# Evap-Lite_V2_1.net
KiCad netlist of a schematic drawn in EAGLE
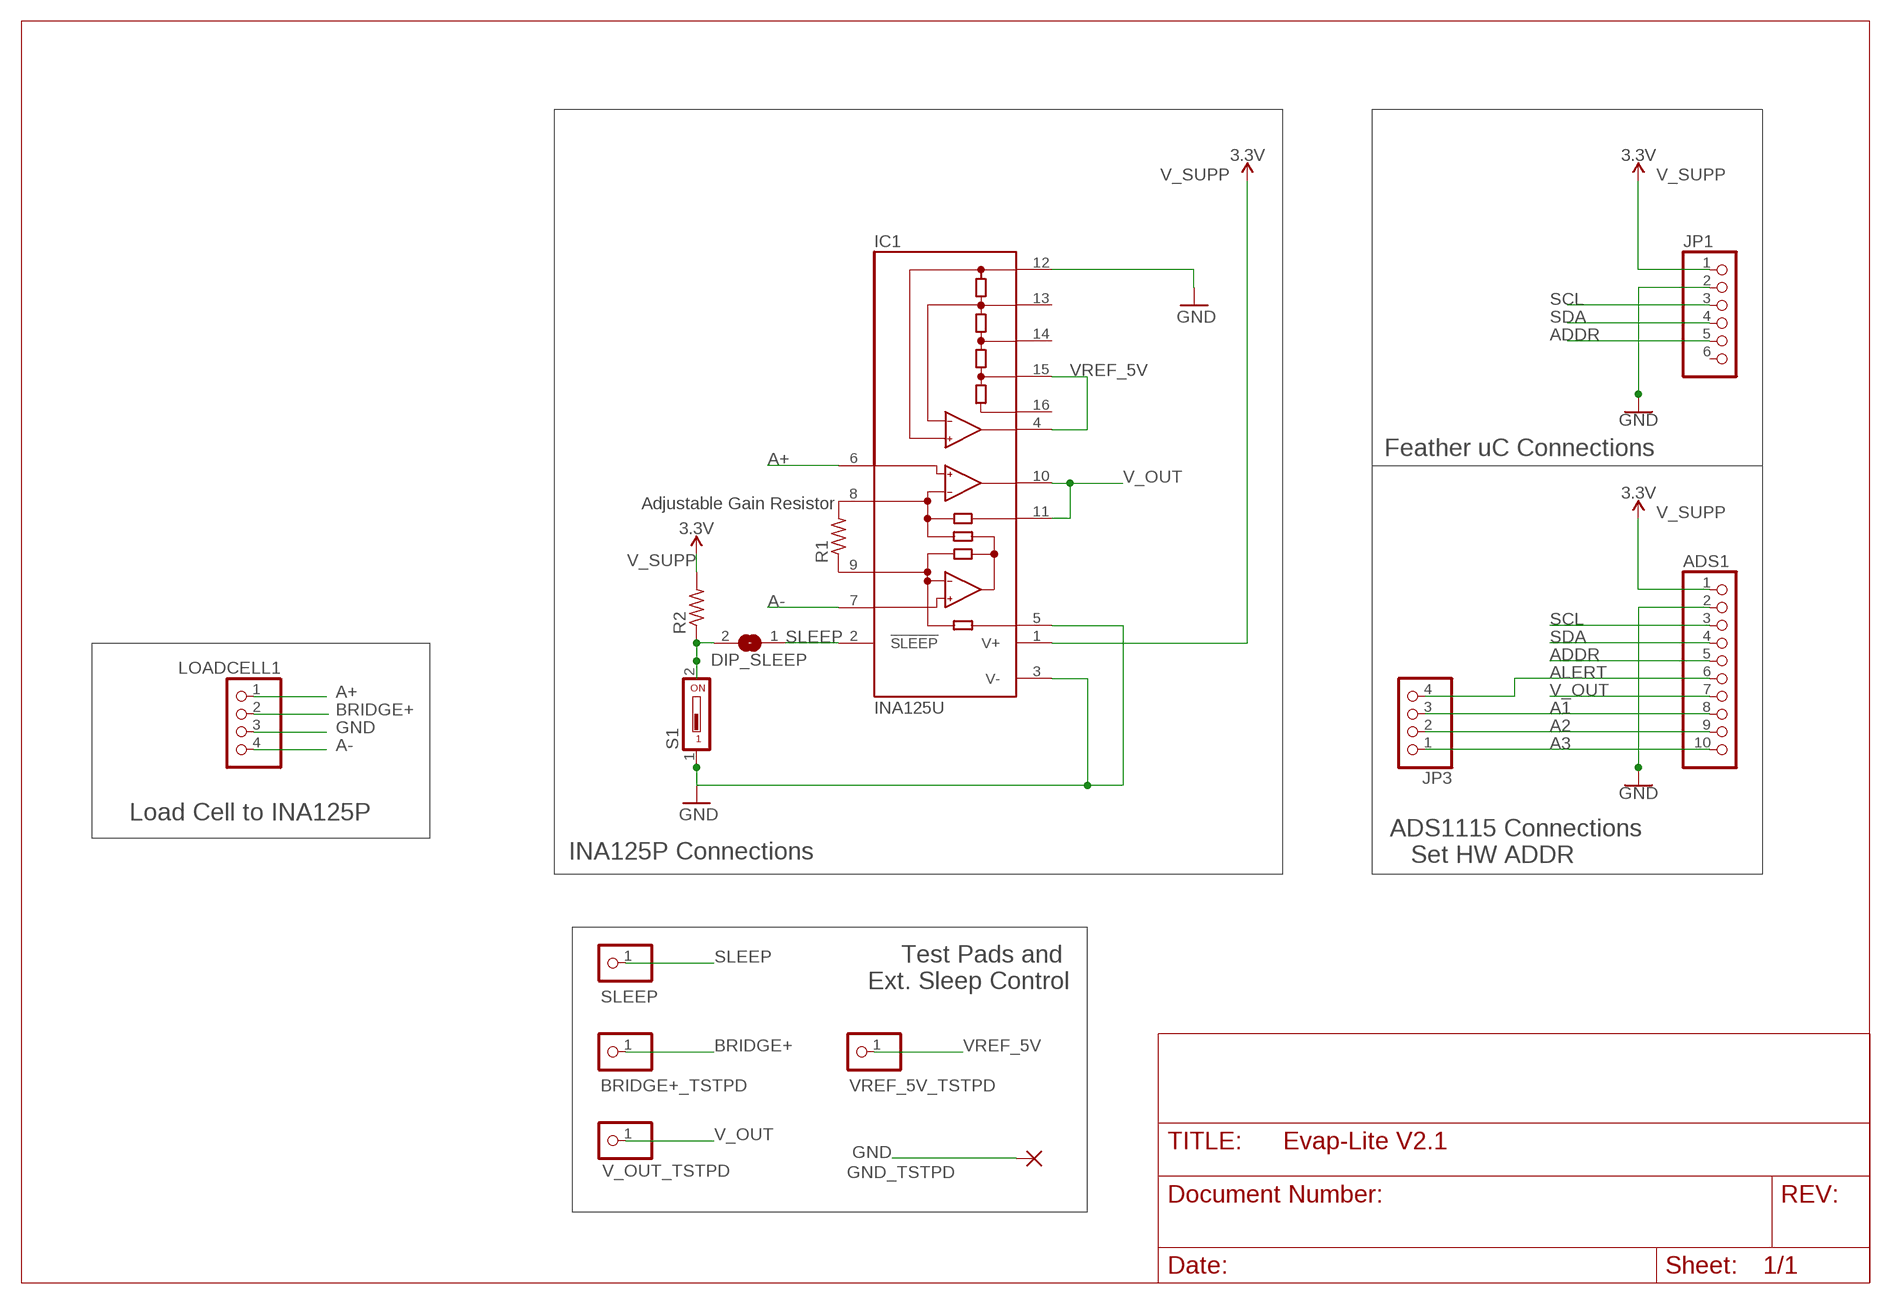
[diagram p0: schematic, sheet 1]

(export (version "E")
  (design (tool "Eeschema 10.0.6"))
  (components
    (comp (ref "ADS1")
      (value "PINHD-1X10")
      (footprint "eagle-import:1X10")
      (libsource (lib "eagle-import") (part "PINHD-1X10"))
    )
    (comp (ref "BRIDGE+_TSTPD")
      (value "PINHD-1X1")
      (footprint "eagle-import:1X01")
      (libsource (lib "eagle-import") (part "PINHD-1X1"))
    )
    (comp (ref "DIP_SLEEP")
      (value "SJ")
      (footprint "eagle-import:SJ")
      (libsource (lib "eagle-import") (part "SJ"))
    )
    (comp (ref "GND_TSTPD")
      (value "WIREPADSMD2,54-5,08")
      (footprint "eagle-import:SMD2,54-5,08")
      (libsource (lib "eagle-import") (part "WIREPADSMD2,54-5,08"))
    )
    (comp (ref "IC1")
      (value "INA125U")
      (footprint "eagle-import:SO16-1")
      (fields (field (name "MF") "TEXAS INSTRUMENT CONNECTORS"))
      (libsource (lib "eagle-import") (part "INA125U"))
    )
    (comp (ref "JP1")
      (value "PINHD-1X6")
      (footprint "eagle-import:1X06")
      (libsource (lib "eagle-import") (part "PINHD-1X6"))
    )
    (comp (ref "JP3")
      (value "PINHD-1X4")
      (footprint "eagle-import:1X04")
      (libsource (lib "eagle-import") (part "PINHD-1X4"))
    )
    (comp (ref "LOADCELL1")
      (value "PINHD-1X4")
      (footprint "eagle-import:1X04")
      (libsource (lib "eagle-import") (part "PINHD-1X4"))
    )
    (comp (ref "R1")
      (value "R-US_R0603")
      (footprint "eagle-import:R0603")
      (libsource (lib "eagle-import") (part "R-US_R0603"))
    )
    (comp (ref "R2")
      (value "R-US_R1206")
      (footprint "eagle-import:R1206")
      (libsource (lib "eagle-import") (part "R-US_R1206"))
    )
    (comp (ref "S1")
      (value "DS01")
      (footprint "eagle-import:DS-01")
      (libsource (lib "eagle-import") (part "DS01"))
    )
    (comp (ref "SLEEP")
      (value "PINHD-1X1")
      (footprint "eagle-import:1X01")
      (libsource (lib "eagle-import") (part "PINHD-1X1"))
    )
    (comp (ref "VREF_5V_TSTPD")
      (value "PINHD-1X1")
      (footprint "eagle-import:1X01")
      (libsource (lib "eagle-import") (part "PINHD-1X1"))
    )
    (comp (ref "V_OUT_TSTPD")
      (value "PINHD-1X1")
      (footprint "eagle-import:1X01")
      (libsource (lib "eagle-import") (part "PINHD-1X1"))
    )
  )
  (nets
    (net (code "1") (name "/A+") (class "Default")
      (node (ref "IC1") (pin "6") (pinfunction "+IN_6") (pintype "input"))
      (node (ref "LOADCELL1") (pin "1") (pinfunction "1_1") (pintype "passive"))
    )
    (net (code "2") (name "/A-") (class "Default")
      (node (ref "IC1") (pin "7") (pinfunction "-IN_7") (pintype "input"))
      (node (ref "LOADCELL1") (pin "4") (pinfunction "4_4") (pintype "passive"))
    )
    (net (code "3") (name "/A1") (class "Default")
      (node (ref "ADS1") (pin "8") (pinfunction "8_8") (pintype "passive"))
      (node (ref "JP3") (pin "3") (pinfunction "3_3") (pintype "passive"))
    )
    (net (code "4") (name "/A2") (class "Default")
      (node (ref "ADS1") (pin "9") (pinfunction "9_9") (pintype "passive"))
      (node (ref "JP3") (pin "2") (pinfunction "2_2") (pintype "passive"))
    )
    (net (code "5") (name "/A3") (class "Default")
      (node (ref "ADS1") (pin "10") (pinfunction "10_10") (pintype "passive"))
      (node (ref "JP3") (pin "1") (pinfunction "1_1") (pintype "passive"))
    )
    (net (code "6") (name "/ADDR") (class "Default")
      (node (ref "ADS1") (pin "5") (pinfunction "5_5") (pintype "passive"))
      (node (ref "JP1") (pin "5") (pinfunction "5_5") (pintype "passive"))
    )
    (net (code "7") (name "/ALERT") (class "Default")
      (node (ref "ADS1") (pin "6") (pinfunction "6_6") (pintype "passive"))
      (node (ref "JP3") (pin "4") (pinfunction "4_4") (pintype "passive"))
    )
    (net (code "8") (name "/BRIDGE+") (class "Default")
      (node (ref "BRIDGE+_TSTPD") (pin "1") (pinfunction "1_1") (pintype "passive"))
      (node (ref "LOADCELL1") (pin "2") (pinfunction "2_2") (pintype "passive"))
    )
    (net (code "9") (name "/SCL") (class "Default")
      (node (ref "ADS1") (pin "3") (pinfunction "3_3") (pintype "passive"))
      (node (ref "JP1") (pin "3") (pinfunction "3_3") (pintype "passive"))
    )
    (net (code "10") (name "/SDA") (class "Default")
      (node (ref "ADS1") (pin "4") (pinfunction "4_4") (pintype "passive"))
      (node (ref "JP1") (pin "4") (pinfunction "4_4") (pintype "passive"))
    )
    (net (code "11") (name "/SLEEP") (class "Default")
      (node (ref "DIP_SLEEP") (pin "1") (pinfunction "1_1") (pintype "passive"))
      (node (ref "IC1") (pin "2") (pinfunction "~{SLEEP}_2") (pintype "input"))
      (node (ref "SLEEP") (pin "1") (pinfunction "1_1") (pintype "passive"))
    )
    (net (code "12") (name "/VREF_5V") (class "Default")
      (node (ref "IC1") (pin "15") (pinfunction "REF5_15") (pintype "output"))
      (node (ref "IC1") (pin "4") (pinfunction "REFOUT_4") (pintype "output"))
      (node (ref "VREF_5V_TSTPD") (pin "1") (pinfunction "1_1") (pintype "passive"))
    )
    (net (code "13") (name "/V_OUT") (class "Default")
      (node (ref "ADS1") (pin "7") (pinfunction "7_7") (pintype "passive"))
      (node (ref "IC1") (pin "10") (pinfunction "OUT_10") (pintype "output"))
      (node (ref "IC1") (pin "11") (pinfunction "SENSE_11") (pintype "passive"))
      (node (ref "V_OUT_TSTPD") (pin "1") (pinfunction "1_1") (pintype "passive"))
    )
    (net (code "14") (name "3.3V") (class "Default")
      (node (ref "ADS1") (pin "1") (pinfunction "1_1") (pintype "passive"))
      (node (ref "IC1") (pin "1") (pinfunction "V+_1") (pintype "power_in"))
      (node (ref "JP1") (pin "1") (pinfunction "1_1") (pintype "passive"))
      (node (ref "R2") (pin "2") (pinfunction "2_2") (pintype "passive"))
    )
    (net (code "15") (name "GND") (class "Default")
      (node (ref "ADS1") (pin "2") (pinfunction "2_2") (pintype "passive"))
      (node (ref "GND_TSTPD") (pin "1") (pinfunction "P_1") (pintype "passive"))
      (node (ref "IC1") (pin "12") (pinfunction "REFCOM_12") (pintype "passive"))
      (node (ref "IC1") (pin "3") (pinfunction "V-_3") (pintype "power_in"))
      (node (ref "IC1") (pin "5") (pinfunction "REF_5") (pintype "passive"))
      (node (ref "JP1") (pin "2") (pinfunction "2_2") (pintype "passive"))
      (node (ref "LOADCELL1") (pin "3") (pinfunction "3_3") (pintype "passive"))
      (node (ref "S1") (pin "1") (pinfunction "1_1") (pintype "passive"))
    )
    (net (code "16") (name "Net-(DIP_SLEEP-Pad2)") (class "Default")
      (node (ref "DIP_SLEEP") (pin "2") (pinfunction "2_2") (pintype "passive"))
      (node (ref "R2") (pin "1") (pinfunction "1_1") (pintype "passive"))
      (node (ref "S1") (pin "2") (pinfunction "2_2") (pintype "passive"))
    )
    (net (code "17") (name "Net-(IC1-RG-Pad8)") (class "Default")
      (node (ref "IC1") (pin "8") (pinfunction "RG_8") (pintype "passive"))
      (node (ref "R1") (pin "2") (pinfunction "2_2") (pintype "passive"))
    )
    (net (code "18") (name "Net-(IC1-RG-Pad9)") (class "Default")
      (node (ref "IC1") (pin "9") (pinfunction "RG_9") (pintype "passive"))
      (node (ref "R1") (pin "1") (pinfunction "1_1") (pintype "passive"))
    )
    (net (code "19") (name "unconnected-(IC1-REF2.5-Pad14)") (class "Default")
      (node (ref "IC1") (pin "14") (pinfunction "REF2.5_14") (pintype "output"))
    )
    (net (code "20") (name "unconnected-(IC1-REF10-Pad16)") (class "Default")
      (node (ref "IC1") (pin "16") (pinfunction "REF10_16") (pintype "output"))
    )
    (net (code "21") (name "unconnected-(IC1-REFBG-Pad13)") (class "Default")
      (node (ref "IC1") (pin "13") (pinfunction "REFBG_13") (pintype "output"))
    )
    (net (code "22") (name "unconnected-(JP1-Pad6)") (class "Default")
      (node (ref "JP1") (pin "6") (pinfunction "6_6") (pintype "passive"))
    )
  )
)
